# current_mp6519.net
KiCad netlist of a schematic drawn in Altium Designer
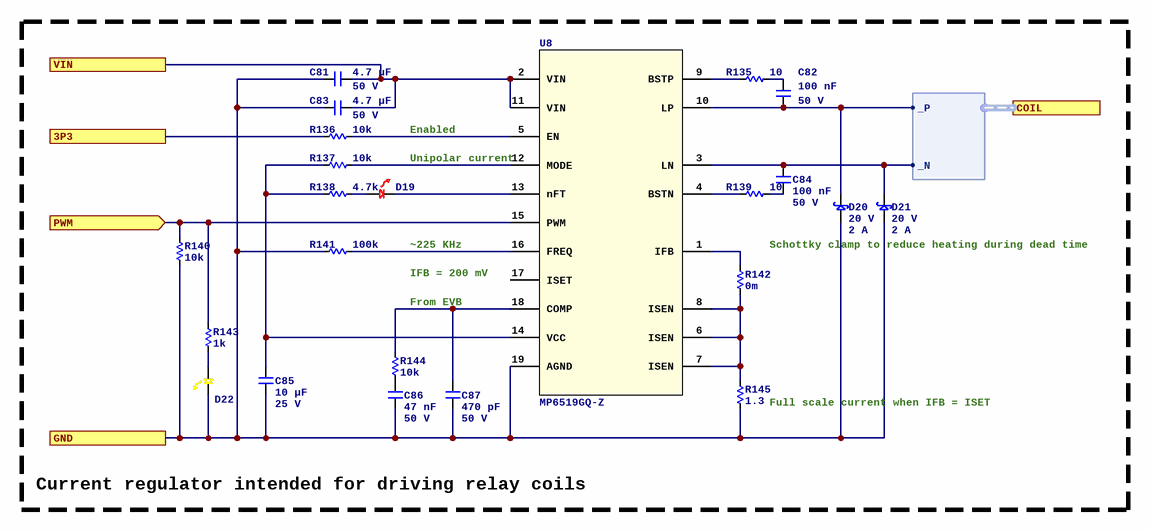
[diagram p0: current_mp6519.SchDoc]

(export (version "E")
  (design (tool "Eeschema 10.0.6"))
  (components
    (comp (ref "C81")
      (value "0805B475K500NT")
      (footprint "C0805")
      (fields
        (field (name "CAPACITANCE") "4.7 µF")
        (field (name "MANUFACTURER") "FH (Guangdong Fenghua Advanced Tech)")
        (field (name "VOLTAGE RATING") "50 V")
      )
      (libsource (lib "database") (part "__template_cap"))
    )
    (comp (ref "C82")
      (value "CL05B104KB54PNC")
      (footprint "C0402")
      (fields
        (field (name "CAPACITANCE") "100 nF")
        (field (name "MANUFACTURER") "Samsung Electro-Mechanics")
        (field (name "VOLTAGE RATING") "50 V")
      )
      (libsource (lib "database") (part "__template_cap"))
    )
    (comp (ref "C83")
      (value "0805B475K500NT")
      (footprint "C0805")
      (fields
        (field (name "CAPACITANCE") "4.7 µF")
        (field (name "MANUFACTURER") "FH (Guangdong Fenghua Advanced Tech)")
        (field (name "VOLTAGE RATING") "50 V")
      )
      (libsource (lib "database") (part "__template_cap"))
    )
    (comp (ref "C84")
      (value "CL05B104KB54PNC")
      (footprint "C0402")
      (fields
        (field (name "CAPACITANCE") "100 nF")
        (field (name "MANUFACTURER") "Samsung Electro-Mechanics")
        (field (name "VOLTAGE RATING") "50 V")
      )
      (libsource (lib "database") (part "__template_cap"))
    )
    (comp (ref "C85")
      (value "CL10A106MA8NRNC")
      (footprint "C0603")
      (fields
        (field (name "CAPACITANCE") "10 µF")
        (field (name "MANUFACTURER") "Samsung Electro-Mechanics")
        (field (name "VOLTAGE RATING") "25 V")
      )
      (libsource (lib "database") (part "__template_cap"))
    )
    (comp (ref "C86")
      (value "0402B473K500NT")
      (footprint "C0402")
      (fields
        (field (name "CAPACITANCE") "47 nF")
        (field (name "MANUFACTURER") "FH(Guangdong Fenghua Advanced Tech)")
        (field (name "VOLTAGE RATING") "50 V")
      )
      (libsource (lib "database") (part "__template_cap"))
    )
    (comp (ref "C87")
      (value "GRM1555C1H471JA01D")
      (footprint "C0402")
      (fields
        (field (name "CAPACITANCE") "470 pF")
        (field (name "MANUFACTURER") "Murata Electronics")
        (field (name "VOLTAGE RATING") "50 V")
      )
      (libsource (lib "database") (part "__template_cap"))
    )
    (comp (ref "D19")
      (value "LTST-C190KRKT")
      (footprint "LED_0603P_RED")
      (description "LED SUPER RED CLEAR 0603 SMD")
      (fields (field (name "MANUFACTURER") "Lite-On Inc"))
      (libsource (lib "database") (part "__template_led_red"))
    )
    (comp (ref "D20")
      (value "MSS2P2-M3/89A")
      (footprint "ESMP")
      (description "DIODE SCHOTTKY 20V 2A MICROSMP")
      (fields
        (field (name "MANUFACTURER") "Vishay Semiconductor Diodes Division")
        (field (name "VR") "20 V")
        (field (name "CURRENT") "2 A")
      )
      (libsource (lib "database") (part "__template_diode_schottky"))
    )
    (comp (ref "D21")
      (value "MSS2P2-M3/89A")
      (footprint "ESMP")
      (description "DIODE SCHOTTKY 20V 2A MICROSMP")
      (fields
        (field (name "MANUFACTURER") "Vishay Semiconductor Diodes Division")
        (field (name "VR") "20 V")
        (field (name "CURRENT") "2 A")
      )
      (libsource (lib "database") (part "__template_diode_schottky"))
    )
    (comp (ref "D22")
      (value "LTST-C190YKT")
      (footprint "LED_0603P_YELLOW")
      (description "LED YELLOW CLEAR 0603 SMD")
      (fields (field (name "MANUFACTURER") "Lite-On Inc"))
      (libsource (lib "database") (part "__template_led_yellow"))
    )
    (comp (ref "R135")
      (value "10")
      (footprint "R0402")
      (fields
        (field (name "TOLERANCE") "1%")
        (field (name "MANUFACTURER PART NUMBER") "FRC0402F10R0TS")
        (field (name "MANUFACTURER") "FOJAN")
      )
      (libsource (lib "database") (part "__template_resistor"))
    )
    (comp (ref "R136")
      (value "10k")
      (footprint "R0402")
      (fields
        (field (name "TOLERANCE") "1%")
        (field (name "MANUFACTURER PART NUMBER") "0402WGF1002TCE")
        (field (name "MANUFACTURER") "UNI-ROYAL(Uniroyal Elec)")
      )
      (libsource (lib "database") (part "__template_resistor"))
    )
    (comp (ref "R137")
      (value "10k")
      (footprint "R0402")
      (fields
        (field (name "TOLERANCE") "1%")
        (field (name "MANUFACTURER PART NUMBER") "0402WGF1002TCE")
        (field (name "MANUFACTURER") "UNI-ROYAL(Uniroyal Elec)")
      )
      (libsource (lib "database") (part "__template_resistor"))
    )
    (comp (ref "R138")
      (value "4.7k")
      (footprint "R0402")
      (fields
        (field (name "TOLERANCE") "1%")
        (field (name "MANUFACTURER PART NUMBER") "0402WGF4701TCE")
        (field (name "MANUFACTURER") "UNI-ROYAL(Uniroyal Elec)")
      )
      (libsource (lib "database") (part "__template_resistor"))
    )
    (comp (ref "R139")
      (value "10")
      (footprint "R0402")
      (fields
        (field (name "TOLERANCE") "1%")
        (field (name "MANUFACTURER PART NUMBER") "FRC0402F10R0TS")
        (field (name "MANUFACTURER") "FOJAN")
      )
      (libsource (lib "database") (part "__template_resistor"))
    )
    (comp (ref "R140")
      (value "10k")
      (footprint "R0402")
      (fields
        (field (name "TOLERANCE") "1%")
        (field (name "MANUFACTURER PART NUMBER") "0402WGF1002TCE")
        (field (name "MANUFACTURER") "UNI-ROYAL(Uniroyal Elec)")
      )
      (libsource (lib "database") (part "__template_resistor"))
    )
    (comp (ref "R141")
      (value "100k")
      (footprint "R0402")
      (fields
        (field (name "TOLERANCE") "1%")
        (field (name "MANUFACTURER PART NUMBER") "0402WGF1003TCE")
        (field (name "MANUFACTURER") "UNI-ROYAL(Uniroyal Elec)")
      )
      (libsource (lib "database") (part "__template_resistor"))
    )
    (comp (ref "R142")
      (value "0m")
      (footprint "R0402")
      (fields
        (field (name "MANUFACTURER PART NUMBER") "0402WGF0000TCE")
        (field (name "MANUFACTURER") "UNI-ROYAL(Uniroyal Elec)")
      )
      (libsource (lib "database") (part "__template_resistor"))
    )
    (comp (ref "R143")
      (value "1k")
      (footprint "R0402")
      (fields
        (field (name "TOLERANCE") "1%")
        (field (name "MANUFACTURER PART NUMBER") "0402WGF1001TCE")
        (field (name "MANUFACTURER") "UNI-ROYAL(Uniroyal Elec)")
      )
      (libsource (lib "database") (part "__template_resistor"))
    )
    (comp (ref "R144")
      (value "10k")
      (footprint "R0402")
      (fields
        (field (name "TOLERANCE") "1%")
        (field (name "MANUFACTURER PART NUMBER") "0402WGF1002TCE")
        (field (name "MANUFACTURER") "UNI-ROYAL(Uniroyal Elec)")
      )
      (libsource (lib "database") (part "__template_resistor"))
    )
    (comp (ref "R145")
      (value "1.3")
      (footprint "R1206")
      (fields
        (field (name "TOLERANCE") "1%")
        (field (name "MANUFACTURER PART NUMBER") "HP06W2F130KT5E")
        (field (name "MANUFACTURER") "UNI-ROYAL(Uniroyal Elec)")
      )
      (libsource (lib "database") (part "__template_resistor"))
    )
    (comp (ref "U8")
      (value "MP6519GQ-Z")
      (footprint "MP6519")
      (description "2.5V - 28V, 5A, H-bridge Current Regulator")
      (fields (field (name "MANUFACTURER") "Monolithic Power Systems"))
      (libsource (lib "database") (part "MP6519GQ-Z"))
    )
  )
  (nets
    (net (code "2") (name "/3P3") (class "Default") (node (ref "R136") (pin "1") (pintype "passive")))
    (net (code "3") (name "/GND") (class "Default")
      (node (ref "C81") (pin "1") (pintype "passive"))
      (node (ref "C83") (pin "1") (pintype "passive"))
      (node (ref "C85") (pin "2") (pintype "passive"))
      (node (ref "C86") (pin "2") (pintype "passive"))
      (node (ref "C87") (pin "2") (pintype "passive"))
      (node (ref "D20") (pin "1") (pintype "passive"))
      (node (ref "D21") (pin "1") (pintype "passive"))
      (node (ref "D22") (pin "2") (pintype "passive"))
      (node (ref "R140") (pin "1") (pintype "passive"))
      (node (ref "R141") (pin "2") (pintype "passive"))
      (node (ref "R145") (pin "1") (pintype "passive"))
      (node (ref "U8") (pin "19") (pinfunction "AGND_19") (pintype "passive"))
    )
    (net (code "4") (name "/PWM") (class "Default")
      (node (ref "R140") (pin "2") (pintype "passive"))
      (node (ref "R143") (pin "1") (pintype "passive"))
      (node (ref "U8") (pin "15") (pinfunction "PWM_15") (pintype "passive"))
    )
    (net (code "5") (name "/VIN") (class "Default")
      (node (ref "C81") (pin "2") (pintype "passive"))
      (node (ref "C83") (pin "2") (pintype "passive"))
      (node (ref "U8") (pin "11") (pinfunction "VIN_11") (pintype "passive"))
      (node (ref "U8") (pin "2") (pinfunction "VIN_2") (pintype "passive"))
    )
    (net (code "7") (name "Net-(C82-Pad1)") (class "Default")
      (node (ref "C82") (pin "1") (pintype "passive"))
      (node (ref "R135") (pin "2") (pintype "passive"))
    )
    (net (code "8") (name "Net-(C84-Pad2)") (class "Default")
      (node (ref "C84") (pin "2") (pintype "passive"))
      (node (ref "R139") (pin "2") (pintype "passive"))
    )
    (net (code "9") (name "Net-(C86-Pad1)") (class "Default")
      (node (ref "C86") (pin "1") (pintype "passive"))
      (node (ref "R144") (pin "1") (pintype "passive"))
    )
    (net (code "10") (name "Net-(D19-Pad1)") (class "Default")
      (node (ref "D19") (pin "1") (pintype "passive"))
      (node (ref "R138") (pin "2") (pintype "passive"))
    )
    (net (code "11") (name "Net-(D22-Pad1)") (class "Default")
      (node (ref "D22") (pin "1") (pintype "passive"))
      (node (ref "R143") (pin "2") (pintype "passive"))
    )
    (net (code "12") (name "Net-(R142-Pad1)") (class "Default")
      (node (ref "R142") (pin "1") (pintype "passive"))
      (node (ref "R145") (pin "2") (pintype "passive"))
      (node (ref "U8") (pin "6") (pinfunction "ISEN_6") (pintype "passive"))
      (node (ref "U8") (pin "7") (pinfunction "ISEN_7") (pintype "passive"))
      (node (ref "U8") (pin "8") (pinfunction "ISEN_8") (pintype "passive"))
    )
    (net (code "13") (name "Net-(U8-BSTN)") (class "Default")
      (node (ref "R139") (pin "1") (pintype "passive"))
      (node (ref "U8") (pin "4") (pinfunction "BSTN_4") (pintype "passive"))
    )
    (net (code "14") (name "Net-(U8-BSTP)") (class "Default")
      (node (ref "R135") (pin "1") (pintype "passive"))
      (node (ref "U8") (pin "9") (pinfunction "BSTP_9") (pintype "passive"))
    )
    (net (code "15") (name "Net-(U8-COMP)") (class "Default")
      (node (ref "C87") (pin "1") (pintype "passive"))
      (node (ref "R144") (pin "2") (pintype "passive"))
      (node (ref "U8") (pin "18") (pinfunction "COMP_18") (pintype "passive"))
    )
    (net (code "16") (name "Net-(U8-EN)") (class "Default")
      (node (ref "R136") (pin "2") (pintype "passive"))
      (node (ref "U8") (pin "5") (pinfunction "EN_5") (pintype "passive"))
    )
    (net (code "17") (name "Net-(U8-FREQ)") (class "Default")
      (node (ref "R141") (pin "1") (pintype "passive"))
      (node (ref "U8") (pin "16") (pinfunction "FREQ_16") (pintype "passive"))
    )
    (net (code "18") (name "Net-(U8-IFB)") (class "Default")
      (node (ref "R142") (pin "2") (pintype "passive"))
      (node (ref "U8") (pin "1") (pinfunction "IFB_1") (pintype "passive"))
    )
    (net (code "19") (name "Net-(U8-LN)") (class "Default")
      (node (ref "C84") (pin "1") (pintype "passive"))
      (node (ref "D21") (pin "2") (pintype "passive"))
      (node (ref "U8") (pin "3") (pinfunction "LN_3") (pintype "passive"))
    )
    (net (code "20") (name "Net-(U8-LP)") (class "Default")
      (node (ref "C82") (pin "2") (pintype "passive"))
      (node (ref "D20") (pin "2") (pintype "passive"))
      (node (ref "U8") (pin "10") (pinfunction "LP_10") (pintype "passive"))
    )
    (net (code "21") (name "Net-(U8-MODE)") (class "Default")
      (node (ref "R137") (pin "2") (pintype "passive"))
      (node (ref "U8") (pin "12") (pinfunction "MODE_12") (pintype "passive"))
    )
    (net (code "22") (name "Net-(U8-VCC)") (class "Default")
      (node (ref "C85") (pin "1") (pintype "passive"))
      (node (ref "R137") (pin "1") (pintype "passive"))
      (node (ref "R138") (pin "1") (pintype "passive"))
      (node (ref "U8") (pin "14") (pinfunction "VCC_14") (pintype "passive"))
    )
    (net (code "23") (name "Net-(U8-nFT)") (class "Default")
      (node (ref "D19") (pin "2") (pintype "passive"))
      (node (ref "U8") (pin "13") (pinfunction "nFT_13") (pintype "passive"))
    )
    (net (code "24") (name "unconnected-(U8-ISET-Pad17)") (class "Default")
      (node (ref "U8") (pin "17") (pinfunction "ISET_17") (pintype "passive"))
    )
  )
)
